# Bidirectional_Voltage_Translator.net
KiCad netlist of a schematic drawn in Altium Designer
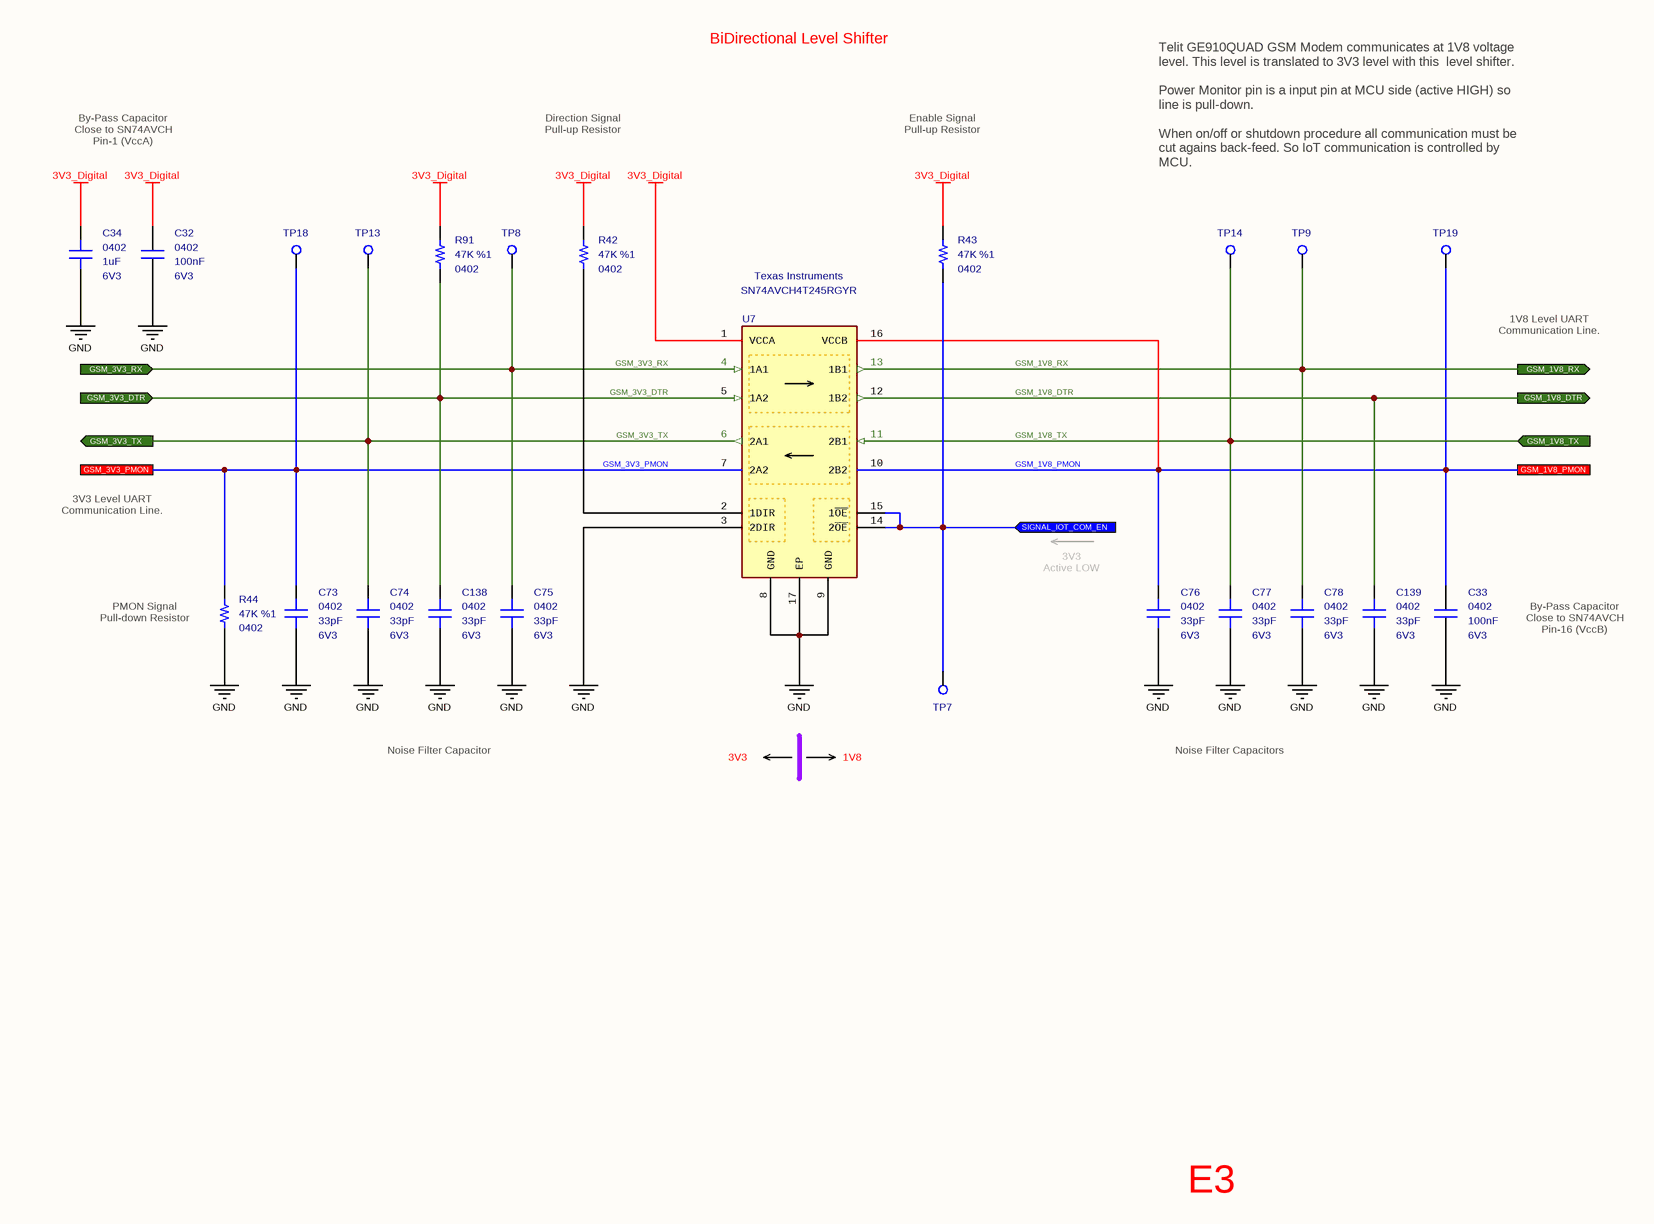
[diagram p0: Bidirectional Voltage Translator.SchDoc]

(export (version "E")
  (design (tool "Eeschema 10.0.6"))
  (components
    (comp (ref "C32")
      (value "100nF")
      (footprint "CAPACITOR_0402")
      (description "Capacitor - 100nF [0402-6V3] (Ceramic)")
      (fields
        (field (name "MANUFACTURER_PART_NUMBER") "04026D104KAT4A")
        (field (name "MOUSER_PART_NUMBER") "581-04026D104KAT4A")
        (field (name "CASE") "0402")
        (field (name "VOLTAGE") "6V3")
      )
      (libsource (lib "Ovoo_Schematic") (part "Capacitor - 100nF [0402-6V3]"))
    )
    (comp (ref "C33")
      (value "100nF")
      (footprint "CAPACITOR_0402")
      (description "Capacitor - 100nF [0402-6V3] (Ceramic)")
      (fields
        (field (name "MANUFACTURER_PART_NUMBER") "04026D104KAT4A")
        (field (name "MOUSER_PART_NUMBER") "581-04026D104KAT4A")
        (field (name "CASE") "0402")
        (field (name "VOLTAGE") "6V3")
      )
      (libsource (lib "Ovoo_Schematic") (part "Capacitor - 100nF [0402-6V3]"))
    )
    (comp (ref "C34")
      (value "1uF")
      (footprint "CAPACITOR_0402")
      (description "Capacitor - 1uF [0402] (Ceramic)")
      (fields
        (field (name "MANUFACTURER_PART_NUMBER") "GRM153R60J105ME95D")
        (field (name "MOUSER_PART_NUMBER") "81-GRM153R60J105ME5D")
        (field (name "CASE") "0402")
        (field (name "VOLTAGE") "6V3")
      )
      (libsource (lib "Ovoo_Schematic") (part "Capacitor - 1uF [0402-6V3)"))
    )
    (comp (ref "C73")
      (value "33pF")
      (footprint "CAPACITOR_0402")
      (description "Capacitor - 33pF [0402] (Ceramic)")
      (fields
        (field (name "MANUFACTURER_PART_NUMBER") "C0402C330J9RACAUTO")
        (field (name "MOUSER_PART_NUMBER") "80-C0402C330J9RAUTO")
        (field (name "CASE") "0402")
        (field (name "VOLTAGE") "6V3")
      )
      (libsource (lib "Ovoo_Schematic") (part "Capacitor - 33pF [0402-6V3]"))
    )
    (comp (ref "C74")
      (value "33pF")
      (footprint "CAPACITOR_0402")
      (description "Capacitor - 33pF [0402] (Ceramic)")
      (fields
        (field (name "MANUFACTURER_PART_NUMBER") "C0402C330J9RACAUTO")
        (field (name "MOUSER_PART_NUMBER") "80-C0402C330J9RAUTO")
        (field (name "CASE") "0402")
        (field (name "VOLTAGE") "6V3")
      )
      (libsource (lib "Ovoo_Schematic") (part "Capacitor - 33pF [0402-6V3]"))
    )
    (comp (ref "C75")
      (value "33pF")
      (footprint "CAPACITOR_0402")
      (description "Capacitor - 33pF [0402] (Ceramic)")
      (fields
        (field (name "MANUFACTURER_PART_NUMBER") "C0402C330J9RACAUTO")
        (field (name "MOUSER_PART_NUMBER") "80-C0402C330J9RAUTO")
        (field (name "CASE") "0402")
        (field (name "VOLTAGE") "6V3")
      )
      (libsource (lib "Ovoo_Schematic") (part "Capacitor - 33pF [0402-6V3]"))
    )
    (comp (ref "C76")
      (value "33pF")
      (footprint "CAPACITOR_0402")
      (description "Capacitor - 33pF [0402] (Ceramic)")
      (fields
        (field (name "MANUFACTURER_PART_NUMBER") "C0402C330J9RACAUTO")
        (field (name "MOUSER_PART_NUMBER") "80-C0402C330J9RAUTO")
        (field (name "CASE") "0402")
        (field (name "VOLTAGE") "6V3")
      )
      (libsource (lib "Ovoo_Schematic") (part "Capacitor - 33pF [0402-6V3]"))
    )
    (comp (ref "C77")
      (value "33pF")
      (footprint "CAPACITOR_0402")
      (description "Capacitor - 33pF [0402] (Ceramic)")
      (fields
        (field (name "MANUFACTURER_PART_NUMBER") "C0402C330J9RACAUTO")
        (field (name "MOUSER_PART_NUMBER") "80-C0402C330J9RAUTO")
        (field (name "CASE") "0402")
        (field (name "VOLTAGE") "6V3")
      )
      (libsource (lib "Ovoo_Schematic") (part "Capacitor - 33pF [0402-6V3]"))
    )
    (comp (ref "C78")
      (value "33pF")
      (footprint "CAPACITOR_0402")
      (description "Capacitor - 33pF [0402] (Ceramic)")
      (fields
        (field (name "MANUFACTURER_PART_NUMBER") "C0402C330J9RACAUTO")
        (field (name "MOUSER_PART_NUMBER") "80-C0402C330J9RAUTO")
        (field (name "CASE") "0402")
        (field (name "VOLTAGE") "6V3")
      )
      (libsource (lib "Ovoo_Schematic") (part "Capacitor - 33pF [0402-6V3]"))
    )
    (comp (ref "C138")
      (value "33pF")
      (footprint "CAPACITOR_0402")
      (description "Capacitor - 33pF [0402] (Ceramic)")
      (fields
        (field (name "MANUFACTURER_PART_NUMBER") "C0402C330J9RACAUTO")
        (field (name "MOUSER_PART_NUMBER") "80-C0402C330J9RAUTO")
        (field (name "CASE") "0402")
        (field (name "VOLTAGE") "6V3")
      )
      (libsource (lib "Ovoo_Schematic") (part "Capacitor - 33pF [0402-6V3]"))
    )
    (comp (ref "C139")
      (value "33pF")
      (footprint "CAPACITOR_0402")
      (description "Capacitor - 33pF [0402] (Ceramic)")
      (fields
        (field (name "MANUFACTURER_PART_NUMBER") "C0402C330J9RACAUTO")
        (field (name "MOUSER_PART_NUMBER") "80-C0402C330J9RAUTO")
        (field (name "CASE") "0402")
        (field (name "VOLTAGE") "6V3")
      )
      (libsource (lib "Ovoo_Schematic") (part "Capacitor - 33pF [0402-6V3]"))
    )
    (comp (ref "R42")
      (value "47K")
      (footprint "RESISTOR_0402")
      (description "Thick Film Resistors - SMD 1/16 W 47 Kohms 1%")
      (fields
        (field (name "MANUFACTURER_PART_NUMBER") "CRCW040247K0FKED")
        (field (name "MOUSER_PART_NUMBER") "71-CRCW0402-47K-E3")
        (field (name "TOLERANCE") "%1")
        (field (name "CASE") "0402")
      )
      (libsource (lib "Ovoo_Schematic") (part "Resistor - 47K"))
    )
    (comp (ref "R43")
      (value "47K")
      (footprint "RESISTOR_0402")
      (description "Thick Film Resistors - SMD 1/16 W 47 Kohms 1%")
      (fields
        (field (name "MANUFACTURER_PART_NUMBER") "CRCW040247K0FKED")
        (field (name "MOUSER_PART_NUMBER") "71-CRCW0402-47K-E3")
        (field (name "TOLERANCE") "%1")
        (field (name "CASE") "0402")
      )
      (libsource (lib "Ovoo_Schematic") (part "Resistor - 47K"))
    )
    (comp (ref "R44")
      (value "47K")
      (footprint "RESISTOR_0402")
      (description "Thick Film Resistors - SMD 1/16 W 47 Kohms 1%")
      (fields
        (field (name "MANUFACTURER_PART_NUMBER") "CRCW040247K0FKED")
        (field (name "MOUSER_PART_NUMBER") "71-CRCW0402-47K-E3")
        (field (name "TOLERANCE") "%1")
        (field (name "CASE") "0402")
      )
      (libsource (lib "Ovoo_Schematic") (part "Resistor - 47K"))
    )
    (comp (ref "R91")
      (value "47K")
      (footprint "RESISTOR_0402")
      (description "Thick Film Resistors - SMD 1/16 W 47 Kohms 1%")
      (fields
        (field (name "MANUFACTURER_PART_NUMBER") "CRCW040247K0FKED")
        (field (name "MOUSER_PART_NUMBER") "71-CRCW0402-47K-E3")
        (field (name "TOLERANCE") "%1")
        (field (name "CASE") "0402")
      )
      (libsource (lib "Ovoo_Schematic") (part "Resistor - 47K"))
    )
    (comp (ref "TP7")
      (value "PCB - Test Point")
      (footprint "Test_Pad - Hole")
      (description "Test Point")
      (libsource (lib "Ovoo_Schematic") (part "PCB - Test Point"))
    )
    (comp (ref "TP8")
      (value "PCB - Test Point")
      (footprint "Test_Pad - Hole")
      (description "Test Point")
      (libsource (lib "Ovoo_Schematic") (part "PCB - Test Point"))
    )
    (comp (ref "TP9")
      (value "PCB - Test Point")
      (footprint "Test_Pad - Hole")
      (description "Test Point")
      (libsource (lib "Ovoo_Schematic") (part "PCB - Test Point"))
    )
    (comp (ref "TP13")
      (value "PCB - Test Point")
      (footprint "Test_Pad - Hole")
      (description "Test Point")
      (libsource (lib "Ovoo_Schematic") (part "PCB - Test Point"))
    )
    (comp (ref "TP14")
      (value "PCB - Test Point")
      (footprint "Test_Pad - Hole")
      (description "Test Point")
      (libsource (lib "Ovoo_Schematic") (part "PCB - Test Point"))
    )
    (comp (ref "TP18")
      (value "PCB - Test Point")
      (footprint "Test_Pad - Hole")
      (description "Test Point")
      (libsource (lib "Ovoo_Schematic") (part "PCB - Test Point"))
    )
    (comp (ref "TP19")
      (value "PCB - Test Point")
      (footprint "Test_Pad - Hole")
      (description "Test Point")
      (libsource (lib "Ovoo_Schematic") (part "PCB - Test Point"))
    )
    (comp (ref "U7")
      (value "Voltage Level Shifter")
      (footprint "VQFN16")
      (description "Translation - Voltage Levels Low Power Dual Channel")
      (fields
        (field (name "MOUSER_PART_NUMBER") "595-SN74AVCH4T245RGY")
        (field (name "MANUFACTURER_NAME") "Texas Instruments")
        (field (name "MANUFACTURER_PART_NUMBER") "SN74AVCH4T245RGYR")
      )
      (libsource (lib "Ovoo_Schematic") (part "IC - SN74AVCH4T245"))
    )
  )
  (nets
    (net (code "1") (name "/GSM_1V8_DTR") (class "Default")
      (node (ref "C139") (pin "2") (pinfunction "2_2") (pintype "passive"))
      (node (ref "U7") (pin "12") (pinfunction "1B2_12") (pintype "output"))
    )
    (net (code "2") (name "/GSM_1V8_PMON") (class "Default")
      (node (ref "C33") (pin "2") (pinfunction "2_2") (pintype "passive"))
      (node (ref "C76") (pin "2") (pinfunction "2_2") (pintype "passive"))
      (node (ref "TP19") (pin "1") (pinfunction "1_1") (pintype "passive"))
      (node (ref "U7") (pin "10") (pinfunction "2B2_10") (pintype "passive"))
      (node (ref "U7") (pin "16") (pinfunction "VCCB_16") (pintype "power_in"))
    )
    (net (code "3") (name "/GSM_1V8_RX") (class "Default")
      (node (ref "C78") (pin "2") (pinfunction "2_2") (pintype "passive"))
      (node (ref "TP9") (pin "1") (pinfunction "1_1") (pintype "passive"))
      (node (ref "U7") (pin "13") (pinfunction "1B1_13") (pintype "output"))
    )
    (net (code "4") (name "/GSM_1V8_TX") (class "Default")
      (node (ref "C77") (pin "2") (pinfunction "2_2") (pintype "passive"))
      (node (ref "TP14") (pin "1") (pinfunction "1_1") (pintype "passive"))
      (node (ref "U7") (pin "11") (pinfunction "2B1_11") (pintype "input"))
    )
    (net (code "5") (name "/GSM_3V3_DTR") (class "Default")
      (node (ref "C138") (pin "2") (pinfunction "2_2") (pintype "passive"))
      (node (ref "R91") (pin "1") (pinfunction "1_1") (pintype "passive"))
      (node (ref "U7") (pin "5") (pinfunction "1A2_5") (pintype "input"))
    )
    (net (code "6") (name "/GSM_3V3_PMON") (class "Default")
      (node (ref "C73") (pin "2") (pinfunction "2_2") (pintype "passive"))
      (node (ref "R44") (pin "2") (pinfunction "2_2") (pintype "passive"))
      (node (ref "TP18") (pin "1") (pinfunction "1_1") (pintype "passive"))
      (node (ref "U7") (pin "7") (pinfunction "2A2_7") (pintype "passive"))
    )
    (net (code "7") (name "/GSM_3V3_RX") (class "Default")
      (node (ref "C75") (pin "2") (pinfunction "2_2") (pintype "passive"))
      (node (ref "TP8") (pin "1") (pinfunction "1_1") (pintype "passive"))
      (node (ref "U7") (pin "4") (pinfunction "1A1_4") (pintype "input"))
    )
    (net (code "8") (name "/GSM_3V3_TX") (class "Default")
      (node (ref "C74") (pin "2") (pinfunction "2_2") (pintype "passive"))
      (node (ref "TP13") (pin "1") (pinfunction "1_1") (pintype "passive"))
      (node (ref "U7") (pin "6") (pinfunction "2A1_6") (pintype "output"))
    )
    (net (code "9") (name "/SIGNAL_IOT_COM_EN") (class "Default")
      (node (ref "R43") (pin "1") (pinfunction "1_1") (pintype "passive"))
      (node (ref "TP7") (pin "1") (pinfunction "1_1") (pintype "passive"))
      (node (ref "U7") (pin "14") (pinfunction "2~{OE}_14") (pintype "passive"))
      (node (ref "U7") (pin "15") (pinfunction "1~{OE}_15") (pintype "passive"))
    )
    (net (code "10") (name "3V3_Digital") (class "Default")
      (node (ref "C32") (pin "2") (pinfunction "2_2") (pintype "passive"))
      (node (ref "C34") (pin "2") (pinfunction "2_2") (pintype "passive"))
      (node (ref "R42") (pin "2") (pinfunction "2_2") (pintype "passive"))
      (node (ref "R43") (pin "2") (pinfunction "2_2") (pintype "passive"))
      (node (ref "R91") (pin "2") (pinfunction "2_2") (pintype "passive"))
      (node (ref "U7") (pin "1") (pinfunction "VCCA_1") (pintype "power_in"))
    )
    (net (code "11") (name "GND") (class "Default")
      (node (ref "C138") (pin "1") (pinfunction "1_1") (pintype "passive"))
      (node (ref "C139") (pin "1") (pinfunction "1_1") (pintype "passive"))
      (node (ref "C32") (pin "1") (pinfunction "1_1") (pintype "passive"))
      (node (ref "C33") (pin "1") (pinfunction "1_1") (pintype "passive"))
      (node (ref "C34") (pin "1") (pinfunction "1_1") (pintype "passive"))
      (node (ref "C73") (pin "1") (pinfunction "1_1") (pintype "passive"))
      (node (ref "C74") (pin "1") (pinfunction "1_1") (pintype "passive"))
      (node (ref "C75") (pin "1") (pinfunction "1_1") (pintype "passive"))
      (node (ref "C76") (pin "1") (pinfunction "1_1") (pintype "passive"))
      (node (ref "C77") (pin "1") (pinfunction "1_1") (pintype "passive"))
      (node (ref "C78") (pin "1") (pinfunction "1_1") (pintype "passive"))
      (node (ref "R44") (pin "1") (pinfunction "1_1") (pintype "passive"))
      (node (ref "U7") (pin "17") (pinfunction "EP_17") (pintype "power_in"))
      (node (ref "U7") (pin "3") (pinfunction "2DIR_3") (pintype "passive"))
      (node (ref "U7") (pin "8") (pinfunction "GND_8") (pintype "power_in"))
      (node (ref "U7") (pin "9") (pinfunction "GND_9") (pintype "power_in"))
    )
    (net (code "12") (name "Net-(U7-1DIR)") (class "Default")
      (node (ref "R42") (pin "1") (pinfunction "1_1") (pintype "passive"))
      (node (ref "U7") (pin "2") (pinfunction "1DIR_2") (pintype "passive"))
    )
  )
)
